# INOUT.net
KiCad netlist of a schematic drawn in Altium Designer
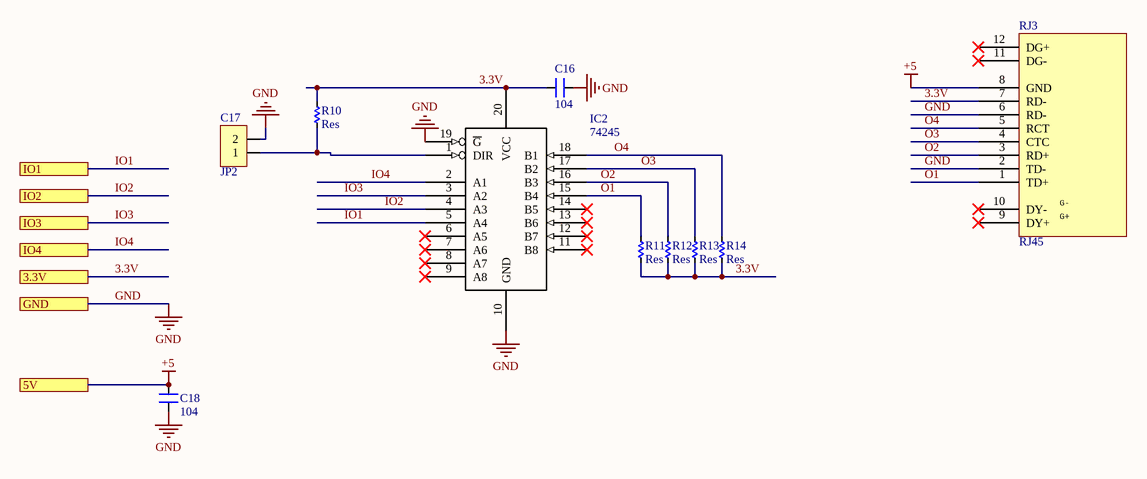
[diagram p0: INOUT.SchDoc]

(export (version "E")
  (design (tool "Eeschema 10.0.6"))
  (components
    (comp (ref "C16")
      (value "104")
      (footprint "SM-Cap-1206")
      (fields (field (name "DESIGNED BY") "VanDungEvn"))
      (libsource (lib "syhaunguyen") (part "CN"))
    )
    (comp (ref "C17")
      (value "JP2")
      (footprint "JP2-CLOSED")
      (description "WR-PHD 2.54 mm Angled Socket Header")
      (fields
        (field (name "MANUFACTURER") "Würth Elektronik eiSos GmbH")
        (field (name "PARTNO") "613002143121")
        (field (name "CREATED BY") "Karrer Zheng")
      )
      (libsource (lib "nhan") (part "JP2"))
    )
    (comp (ref "C18")
      (value "104")
      (footprint "SM-Cap-1206")
      (fields (field (name "DESIGNED BY") "VanDungEvn"))
      (libsource (lib "syhaunguyen") (part "CN"))
    )
    (comp (ref "IC2")
      (value "74245")
      (footprint "SO20")
      (description "Octal bus tranceiver; 3-state")
      (fields (field (name "COPYRIGHT BY") "VanDungEvn@gmail.com"))
      (libsource (lib "BanLinhKien") (part "74245"))
    )
    (comp (ref "R10")
      (value "Res")
      (footprint "RES-SMD-0805")
      (description "Resistor")
      (fields
        (field (name "MANUFACTURER") "Generic Components")
        (field (name "PUBLISHER") "Altium Hobart Technology Centre")
      )
      (libsource (lib "BanLinhKien") (part "Res-SMD"))
    )
    (comp (ref "R11")
      (value "Res")
      (footprint "RES-SMD-0805")
      (description "Resistor")
      (fields
        (field (name "MANUFACTURER") "Generic Components")
        (field (name "PUBLISHER") "Altium Hobart Technology Centre")
      )
      (libsource (lib "BanLinhKien") (part "Res-SMD"))
    )
    (comp (ref "R12")
      (value "Res")
      (footprint "RES-SMD-0805")
      (description "Resistor")
      (fields
        (field (name "MANUFACTURER") "Generic Components")
        (field (name "PUBLISHER") "Altium Hobart Technology Centre")
      )
      (libsource (lib "BanLinhKien") (part "Res-SMD"))
    )
    (comp (ref "R13")
      (value "Res")
      (footprint "RES-SMD-0805")
      (description "Resistor")
      (fields
        (field (name "MANUFACTURER") "Generic Components")
        (field (name "PUBLISHER") "Altium Hobart Technology Centre")
      )
      (libsource (lib "BanLinhKien") (part "Res-SMD"))
    )
    (comp (ref "R14")
      (value "Res")
      (footprint "RES-SMD-0805")
      (description "Resistor")
      (fields
        (field (name "MANUFACTURER") "Generic Components")
        (field (name "PUBLISHER") "Altium Hobart Technology Centre")
      )
      (libsource (lib "BanLinhKien") (part "Res-SMD"))
    )
    (comp (ref "RJ3") (value "RJ45") (footprint "RJ45-Dung") (libsource (lib "nhan") (part "CON JR45")))
  )
  (nets
    (net (code "1") (name "+5") (class "Default")
      (node (ref "C18") (pin "2") (pinfunction "2_2") (pintype "passive"))
      (node (ref "RJ3") (pin "8") (pinfunction "GND_8") (pintype "power_in"))
    )
    (net (code "2") (name "/3.3V") (class "Default")
      (node (ref "C16") (pin "1") (pinfunction "1_1") (pintype "passive"))
      (node (ref "IC2") (pin "20") (pinfunction "VCC_20") (pintype "power_in"))
      (node (ref "R10") (pin "1") (pinfunction "1_1") (pintype "passive"))
      (node (ref "R11") (pin "2") (pinfunction "2_2") (pintype "passive"))
      (node (ref "R12") (pin "2") (pinfunction "2_2") (pintype "passive"))
      (node (ref "R13") (pin "2") (pinfunction "2_2") (pintype "passive"))
      (node (ref "R14") (pin "2") (pinfunction "2_2") (pintype "passive"))
      (node (ref "RJ3") (pin "7") (pinfunction "RD-_7") (pintype "passive"))
    )
    (net (code "3") (name "/IO1") (class "Default")
      (node (ref "IC2") (pin "5") (pinfunction "A4_5") (pintype "tri_state"))
    )
    (net (code "4") (name "/IO2") (class "Default")
      (node (ref "IC2") (pin "4") (pinfunction "A3_4") (pintype "tri_state"))
    )
    (net (code "5") (name "/IO3") (class "Default")
      (node (ref "IC2") (pin "3") (pinfunction "A2_3") (pintype "tri_state"))
    )
    (net (code "6") (name "/IO4") (class "Default")
      (node (ref "IC2") (pin "2") (pinfunction "A1_2") (pintype "tri_state"))
    )
    (net (code "7") (name "/O1") (class "Default")
      (node (ref "IC2") (pin "15") (pinfunction "B4_15") (pintype "input"))
      (node (ref "R11") (pin "1") (pinfunction "1_1") (pintype "passive"))
      (node (ref "RJ3") (pin "1") (pinfunction "TD+_1") (pintype "passive"))
    )
    (net (code "8") (name "/O2") (class "Default")
      (node (ref "IC2") (pin "16") (pinfunction "B3_16") (pintype "input"))
      (node (ref "R12") (pin "1") (pinfunction "1_1") (pintype "passive"))
      (node (ref "RJ3") (pin "3") (pinfunction "RD+_3") (pintype "passive"))
    )
    (net (code "9") (name "/O3") (class "Default")
      (node (ref "IC2") (pin "17") (pinfunction "B2_17") (pintype "input"))
      (node (ref "R13") (pin "1") (pinfunction "1_1") (pintype "passive"))
      (node (ref "RJ3") (pin "4") (pinfunction "CTC_4") (pintype "passive"))
    )
    (net (code "10") (name "/O4") (class "Default")
      (node (ref "IC2") (pin "18") (pinfunction "B1_18") (pintype "input"))
      (node (ref "R14") (pin "1") (pinfunction "1_1") (pintype "passive"))
      (node (ref "RJ3") (pin "5") (pinfunction "RCT_5") (pintype "passive"))
    )
    (net (code "11") (name "GND") (class "Default")
      (node (ref "C16") (pin "2") (pinfunction "2_2") (pintype "passive"))
      (node (ref "C17") (pin "2") (pinfunction "2_2") (pintype "passive"))
      (node (ref "C18") (pin "1") (pinfunction "1_1") (pintype "passive"))
      (node (ref "IC2") (pin "10") (pinfunction "GND_10") (pintype "power_in"))
      (node (ref "IC2") (pin "19") (pinfunction "~{G}_19") (pintype "input"))
      (node (ref "RJ3") (pin "2") (pinfunction "TD-_2") (pintype "passive"))
      (node (ref "RJ3") (pin "6") (pinfunction "RD-_6") (pintype "passive"))
    )
    (net (code "12") (name "Net-(IC2-DIR)") (class "Default")
      (node (ref "C17") (pin "1") (pinfunction "1_1") (pintype "passive"))
      (node (ref "IC2") (pin "1") (pinfunction "DIR_1") (pintype "input"))
      (node (ref "R10") (pin "2") (pinfunction "2_2") (pintype "passive"))
    )
    (net (code "13") (name "unconnected-(IC2-A5-Pad6)") (class "Default")
      (node (ref "IC2") (pin "6") (pinfunction "A5_6") (pintype "tri_state+no_connect"))
    )
    (net (code "14") (name "unconnected-(IC2-A6-Pad7)") (class "Default")
      (node (ref "IC2") (pin "7") (pinfunction "A6_7") (pintype "tri_state+no_connect"))
    )
    (net (code "15") (name "unconnected-(IC2-A7-Pad8)") (class "Default")
      (node (ref "IC2") (pin "8") (pinfunction "A7_8") (pintype "tri_state+no_connect"))
    )
    (net (code "16") (name "unconnected-(IC2-A8-Pad9)") (class "Default")
      (node (ref "IC2") (pin "9") (pinfunction "A8_9") (pintype "tri_state+no_connect"))
    )
    (net (code "17") (name "unconnected-(IC2-B5-Pad14)") (class "Default")
      (node (ref "IC2") (pin "14") (pinfunction "B5_14") (pintype "input+no_connect"))
    )
    (net (code "18") (name "unconnected-(IC2-B6-Pad13)") (class "Default")
      (node (ref "IC2") (pin "13") (pinfunction "B6_13") (pintype "input+no_connect"))
    )
    (net (code "19") (name "unconnected-(IC2-B7-Pad12)") (class "Default")
      (node (ref "IC2") (pin "12") (pinfunction "B7_12") (pintype "input+no_connect"))
    )
    (net (code "20") (name "unconnected-(IC2-B8-Pad11)") (class "Default")
      (node (ref "IC2") (pin "11") (pinfunction "B8_11") (pintype "input+no_connect"))
    )
    (net (code "21") (name "unconnected-(RJ3-DG+-Pad12)") (class "Default")
      (node (ref "RJ3") (pin "12") (pinfunction "DG+_12") (pintype "passive+no_connect"))
    )
    (net (code "22") (name "unconnected-(RJ3-DG--Pad11)") (class "Default")
      (node (ref "RJ3") (pin "11") (pinfunction "DG-_11") (pintype "passive+no_connect"))
    )
    (net (code "23") (name "unconnected-(RJ3-DY+-Pad9)") (class "Default")
      (node (ref "RJ3") (pin "9") (pinfunction "DY+_9") (pintype "passive+no_connect"))
    )
    (net (code "24") (name "unconnected-(RJ3-DY--Pad10)") (class "Default")
      (node (ref "RJ3") (pin "10") (pinfunction "DY-_10") (pintype "passive+no_connect"))
    )
  )
)
